# DMX_isolated.net
KiCad netlist of a schematic drawn in EAGLE
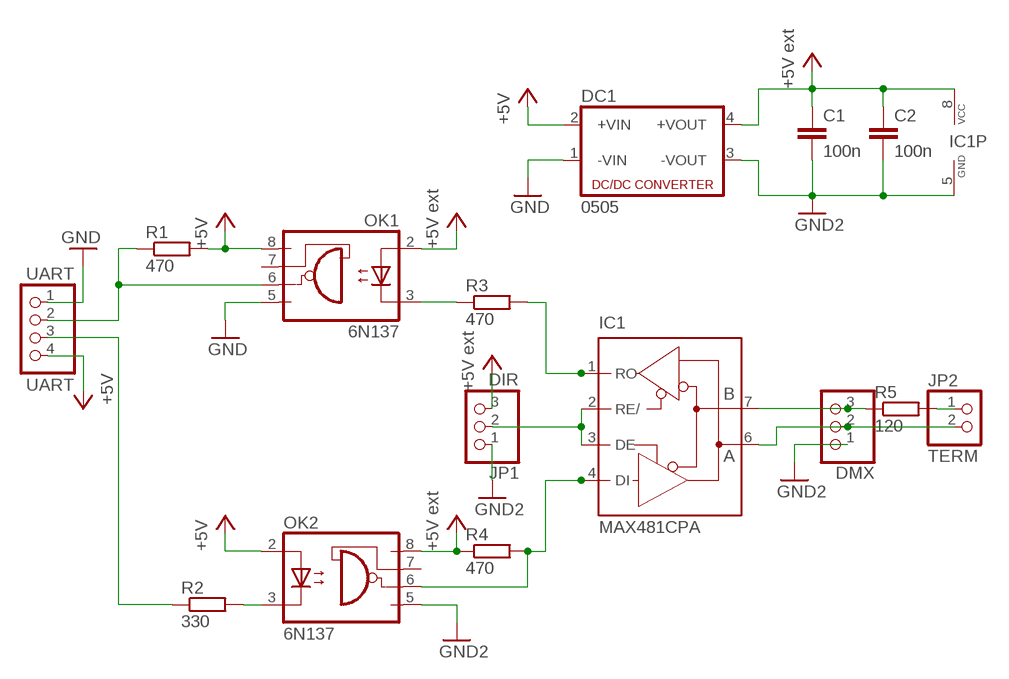
[diagram p0: schematic, sheet 1]

(export (version "E")
  (design (tool "Eeschema 10.0.6"))
  (components
    (comp (ref "C1")
      (value "100n")
      (footprint "eagle-import:C050-024X044")
      (libsource (lib "eagle-import") (part "C-EU050-024X044"))
    )
    (comp (ref "C2")
      (value "100n")
      (footprint "eagle-import:C050-024X044")
      (libsource (lib "eagle-import") (part "C-EU050-024X044"))
    )
    (comp (ref "DC1")
      (value "0505")
      (footprint "eagle-import:NME")
      (fields (field (name "MF") "C & D TECHNOLOGIES, INC") (field (name "MPN") "NME1205D"))
      (libsource (lib "eagle-import") (part "NME"))
    )
    (comp (ref "DMX")
      (value "PINHD-1X3")
      (footprint "eagle-import:1X03")
      (libsource (lib "eagle-import") (part "pinhead_PINHD-1X3"))
    )
    (comp (ref "IC1")
      (value "MAX481CPA")
      (footprint "eagle-import:DIL08")
      (fields (field (name "MPN") "MAX481CPA+"))
      (libsource (lib "eagle-import") (part "MAX481CPA"))
    )
    (comp (ref "JP1")
      (value "DIR")
      (footprint "eagle-import:1X03")
      (libsource (lib "eagle-import") (part "PINHD-1X3"))
    )
    (comp (ref "JP2")
      (value "TERM")
      (footprint "eagle-import:1X02")
      (libsource (lib "eagle-import") (part "PINHD-1X2"))
    )
    (comp (ref "OK1")
      (value "6N137")
      (footprint "eagle-import:DIL08")
      (libsource (lib "eagle-import") (part "6N137"))
    )
    (comp (ref "OK2")
      (value "6N137")
      (footprint "eagle-import:DIL08")
      (libsource (lib "eagle-import") (part "6N137"))
    )
    (comp (ref "R1")
      (value "470")
      (footprint "eagle-import:0204_5")
      (libsource (lib "eagle-import") (part "R-EU_0204/5"))
    )
    (comp (ref "R2")
      (value "330")
      (footprint "eagle-import:0204_5")
      (libsource (lib "eagle-import") (part "R-EU_0204/5"))
    )
    (comp (ref "R3")
      (value "470")
      (footprint "eagle-import:0204_5")
      (libsource (lib "eagle-import") (part "R-EU_0204/5"))
    )
    (comp (ref "R4")
      (value "470")
      (footprint "eagle-import:0204V")
      (libsource (lib "eagle-import") (part "R-EU_0204/2V"))
    )
    (comp (ref "R5")
      (value "120")
      (footprint "eagle-import:0204V")
      (libsource (lib "eagle-import") (part "R-EU_0204/2V"))
    )
    (comp (ref "UART")
      (value "UART")
      (footprint "eagle-import:1X04")
      (libsource (lib "eagle-import") (part "PINHD-1X4"))
    )
  )
  (nets
    (net (code "1") (name "+5V") (class "Default")
      (node (ref "DC1") (pin "2") (pinfunction "+VIN_2") (pintype "passive"))
      (node (ref "OK1") (pin "8") (pinfunction "VCC_8") (pintype "passive"))
      (node (ref "OK2") (pin "2") (pinfunction "A_2") (pintype "passive"))
      (node (ref "R1") (pin "2") (pinfunction "2_2") (pintype "passive"))
      (node (ref "UART") (pin "4") (pinfunction "4_4") (pintype "passive"))
    )
    (net (code "2") (name "+5V ext") (class "Default")
      (node (ref "C1") (pin "1") (pinfunction "1_1") (pintype "passive"))
      (node (ref "C2") (pin "1") (pinfunction "1_1") (pintype "passive"))
      (node (ref "DC1") (pin "4") (pinfunction "+VOUT_4") (pintype "passive"))
      (node (ref "IC1") (pin "8") (pinfunction "VCC_8") (pintype "power_in"))
      (node (ref "JP1") (pin "3") (pinfunction "3_3") (pintype "passive"))
      (node (ref "OK1") (pin "2") (pinfunction "A_2") (pintype "passive"))
      (node (ref "OK2") (pin "8") (pinfunction "VCC_8") (pintype "passive"))
      (node (ref "R4") (pin "1") (pinfunction "1_1") (pintype "passive"))
    )
    (net (code "3") (name "GND") (class "Default")
      (node (ref "DC1") (pin "1") (pinfunction "-VIN_1") (pintype "passive"))
      (node (ref "OK1") (pin "5") (pinfunction "GND_5") (pintype "passive"))
      (node (ref "UART") (pin "1") (pinfunction "1_1") (pintype "passive"))
    )
    (net (code "4") (name "GND2") (class "Default")
      (node (ref "C1") (pin "2") (pinfunction "2_2") (pintype "passive"))
      (node (ref "C2") (pin "2") (pinfunction "2_2") (pintype "passive"))
      (node (ref "DC1") (pin "3") (pinfunction "-VOUT_3") (pintype "passive"))
      (node (ref "DMX") (pin "1") (pinfunction "1_1") (pintype "passive"))
      (node (ref "IC1") (pin "5") (pinfunction "GND_5") (pintype "power_in"))
      (node (ref "JP1") (pin "1") (pinfunction "1_1") (pintype "passive"))
      (node (ref "OK2") (pin "5") (pinfunction "GND_5") (pintype "passive"))
    )
    (net (code "5") (name "Net-(IC1A-A)") (class "Default")
      (node (ref "DMX") (pin "2") (pinfunction "2_2") (pintype "passive"))
      (node (ref "IC1") (pin "6") (pinfunction "A_6") (pintype "passive"))
      (node (ref "JP2") (pin "2") (pinfunction "2_2") (pintype "passive"))
    )
    (net (code "6") (name "Net-(IC1A-B)") (class "Default")
      (node (ref "DMX") (pin "3") (pinfunction "3_3") (pintype "passive"))
      (node (ref "IC1") (pin "7") (pinfunction "B_7") (pintype "passive"))
      (node (ref "R5") (pin "1") (pinfunction "1_1") (pintype "passive"))
    )
    (net (code "7") (name "Net-(IC1A-DE)") (class "Default")
      (node (ref "IC1") (pin "2") (pinfunction "RE/_2") (pintype "input"))
      (node (ref "IC1") (pin "3") (pinfunction "DE_3") (pintype "input"))
      (node (ref "JP1") (pin "2") (pinfunction "2_2") (pintype "passive"))
    )
    (net (code "8") (name "Net-(IC1A-DI)") (class "Default")
      (node (ref "IC1") (pin "4") (pinfunction "DI_4") (pintype "input"))
      (node (ref "OK2") (pin "6") (pinfunction "VO_6") (pintype "passive"))
      (node (ref "R4") (pin "2") (pinfunction "2_2") (pintype "passive"))
    )
    (net (code "9") (name "Net-(IC1A-RO)") (class "Default")
      (node (ref "IC1") (pin "1") (pinfunction "RO_1") (pintype "output"))
      (node (ref "R3") (pin "2") (pinfunction "2_2") (pintype "passive"))
    )
    (net (code "10") (name "Net-(JP2-Pad1)") (class "Default")
      (node (ref "JP2") (pin "1") (pinfunction "1_1") (pintype "passive"))
      (node (ref "R5") (pin "2") (pinfunction "2_2") (pintype "passive"))
    )
    (net (code "11") (name "Net-(OK1-C)") (class "Default")
      (node (ref "OK1") (pin "3") (pinfunction "C_3") (pintype "passive"))
      (node (ref "R3") (pin "1") (pinfunction "1_1") (pintype "passive"))
    )
    (net (code "12") (name "Net-(OK1-VO)") (class "Default")
      (node (ref "OK1") (pin "6") (pinfunction "VO_6") (pintype "passive"))
      (node (ref "R1") (pin "1") (pinfunction "1_1") (pintype "passive"))
      (node (ref "UART") (pin "2") (pinfunction "2_2") (pintype "passive"))
    )
    (net (code "13") (name "Net-(OK2-C)") (class "Default")
      (node (ref "OK2") (pin "3") (pinfunction "C_3") (pintype "passive"))
      (node (ref "R2") (pin "2") (pinfunction "2_2") (pintype "passive"))
    )
    (net (code "14") (name "Net-(R2-Pad1)") (class "Default")
      (node (ref "R2") (pin "1") (pinfunction "1_1") (pintype "passive"))
      (node (ref "UART") (pin "3") (pinfunction "3_3") (pintype "passive"))
    )
    (net (code "15") (name "unconnected-(OK1-VE-Pad7)") (class "Default")
      (node (ref "OK1") (pin "7") (pinfunction "VE_7") (pintype "passive"))
    )
    (net (code "16") (name "unconnected-(OK2-VE-Pad7)") (class "Default")
      (node (ref "OK2") (pin "7") (pinfunction "VE_7") (pintype "passive"))
    )
  )
)
